# Inchworm_v0.net
KiCad netlist of a schematic drawn in Altium Designer
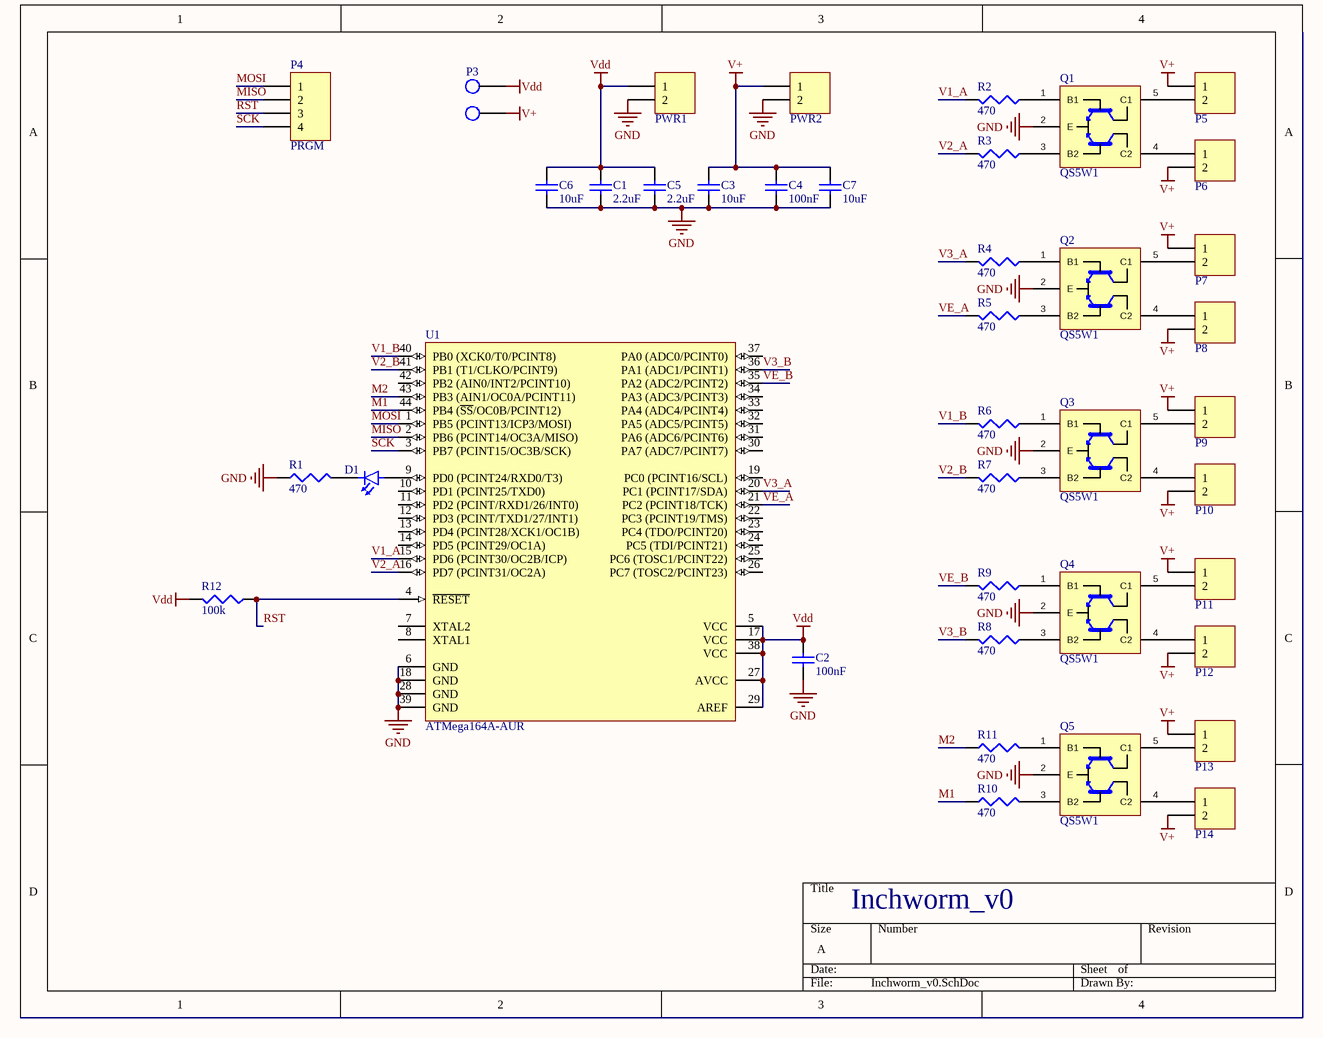
[diagram p0: Inchworm_v0.SchDoc]

(export (version "E")
  (design (tool "Eeschema 10.0.6"))
  (components
    (comp (ref "C1")
      (value "2.2uF")
      (footprint "SMD0603_cap")
      (description "Ceramic Chip Capacitor")
      (fields (field (name "Comment") "Cap"))
      (libsource (lib "Components") (part "Capacitor Ceramic"))
    )
    (comp (ref "C2")
      (value "100nF")
      (footprint "SMD0603_cap")
      (description "Ceramic Chip Capacitor")
      (fields (field (name "Comment") "Cap"))
      (libsource (lib "Components") (part "Capacitor Ceramic"))
    )
    (comp (ref "C3")
      (value "10uF")
      (footprint "SMD0603_cap")
      (description "Ceramic Chip Capacitor")
      (fields (field (name "Comment") "Cap"))
      (libsource (lib "Components") (part "Capacitor Ceramic"))
    )
    (comp (ref "C4")
      (value "100nF")
      (footprint "SMD0603_cap")
      (description "Ceramic Chip Capacitor")
      (fields (field (name "Comment") "Cap"))
      (libsource (lib "Components") (part "Capacitor Ceramic"))
    )
    (comp (ref "C5")
      (value "2.2uF")
      (footprint "SMD0603_cap")
      (description "Ceramic Chip Capacitor")
      (fields (field (name "Comment") "Cap"))
      (libsource (lib "Components") (part "Capacitor Ceramic"))
    )
    (comp (ref "C6")
      (value "10uF")
      (footprint "SMD0603_cap")
      (description "Ceramic Chip Capacitor")
      (fields (field (name "Comment") "Cap"))
      (libsource (lib "Components") (part "Capacitor Ceramic"))
    )
    (comp (ref "C7")
      (value "10uF")
      (footprint "SMD0603_cap")
      (description "Ceramic Chip Capacitor")
      (fields (field (name "Comment") "Cap"))
      (libsource (lib "Components") (part "Capacitor Ceramic"))
    )
    (comp (ref "D1")
      (value "LED")
      (footprint "SMD0603 POLARIZED")
      (libsource (lib "Components") (part "LED"))
    )
    (comp (ref "P1")
      (value "PWR1")
      (footprint "Header 2x1")
      (description "Header, 2-Pin")
      (libsource (lib "Components") (part "Header 2x1"))
    )
    (comp (ref "P2")
      (value "PWR2")
      (footprint "Header 2x1")
      (description "Header, 2-Pin")
      (libsource (lib "Components") (part "Header 2x1"))
    )
    (comp (ref "P3") (value "Via 2x1") (footprint "Via 2x1") (libsource (lib "Components") (part "Via 2x1")))
    (comp (ref "P4")
      (value "PRGM")
      (footprint "Header 4x1")
      (libsource (lib "Components") (part "Header 4x1"))
    )
    (comp (ref "P5")
      (value "Header")
      (footprint "Via 2x1_small")
      (description "Header, 2-Pin")
      (libsource (lib "Components") (part "Header 2x1"))
    )
    (comp (ref "P6")
      (value "Header")
      (footprint "Via 2x1_small")
      (description "Header, 2-Pin")
      (libsource (lib "Components") (part "Header 2x1"))
    )
    (comp (ref "P7")
      (value "Header")
      (footprint "Via 2x1_small")
      (description "Header, 2-Pin")
      (libsource (lib "Components") (part "Header 2x1"))
    )
    (comp (ref "P8")
      (value "Header")
      (footprint "Via 2x1_small")
      (description "Header, 2-Pin")
      (libsource (lib "Components") (part "Header 2x1"))
    )
    (comp (ref "P9")
      (value "Header")
      (footprint "Via 2x1_small")
      (description "Header, 2-Pin")
      (libsource (lib "Components") (part "Header 2x1"))
    )
    (comp (ref "P10")
      (value "Header")
      (footprint "Via 2x1_small")
      (description "Header, 2-Pin")
      (libsource (lib "Components") (part "Header 2x1"))
    )
    (comp (ref "P11")
      (value "Header")
      (footprint "Via 2x1_small")
      (description "Header, 2-Pin")
      (libsource (lib "Components") (part "Header 2x1"))
    )
    (comp (ref "P12")
      (value "Header")
      (footprint "Via 2x1_small")
      (description "Header, 2-Pin")
      (libsource (lib "Components") (part "Header 2x1"))
    )
    (comp (ref "P13")
      (value "Header")
      (footprint "Via 2x1_small")
      (description "Header, 2-Pin")
      (libsource (lib "Components") (part "Header 2x1"))
    )
    (comp (ref "P14")
      (value "Header")
      (footprint "Via 2x1_small")
      (description "Header, 2-Pin")
      (libsource (lib "Components") (part "Header 2x1"))
    )
    (comp (ref "Q1")
      (value "QS5W1")
      (footprint "TSMT5")
      (description "Two Medium-Power NPN BJTs with Common Emitter.  Rohm Semi.")
      (libsource (lib "Components") (part "QS5W1"))
    )
    (comp (ref "Q2")
      (value "QS5W1")
      (footprint "TSMT5")
      (description "Two Medium-Power NPN BJTs with Common Emitter.  Rohm Semi.")
      (libsource (lib "Components") (part "QS5W1"))
    )
    (comp (ref "Q3")
      (value "QS5W1")
      (footprint "TSMT5")
      (description "Two Medium-Power NPN BJTs with Common Emitter.  Rohm Semi.")
      (libsource (lib "Components") (part "QS5W1"))
    )
    (comp (ref "Q4")
      (value "QS5W1")
      (footprint "TSMT5")
      (description "Two Medium-Power NPN BJTs with Common Emitter.  Rohm Semi.")
      (libsource (lib "Components") (part "QS5W1"))
    )
    (comp (ref "Q5")
      (value "QS5W1")
      (footprint "TSMT5")
      (description "Two Medium-Power NPN BJTs with Common Emitter.  Rohm Semi.")
      (libsource (lib "Components") (part "QS5W1"))
    )
    (comp (ref "R1")
      (value "470")
      (footprint "SMD0603_res")
      (description "Resistor")
      (fields (field (name "Comment") "Res"))
      (libsource (lib "Components") (part "Resistor"))
    )
    (comp (ref "R2")
      (value "470")
      (footprint "SMD0603_res")
      (description "Resistor")
      (fields (field (name "Comment") "Res"))
      (libsource (lib "Components") (part "Resistor"))
    )
    (comp (ref "R3")
      (value "470")
      (footprint "SMD0603_res")
      (description "Resistor")
      (fields (field (name "Comment") "Res"))
      (libsource (lib "Components") (part "Resistor"))
    )
    (comp (ref "R4")
      (value "470")
      (footprint "SMD0603_res")
      (description "Resistor")
      (fields (field (name "Comment") "Res"))
      (libsource (lib "Components") (part "Resistor"))
    )
    (comp (ref "R5")
      (value "470")
      (footprint "SMD0603_res")
      (description "Resistor")
      (fields (field (name "Comment") "Res"))
      (libsource (lib "Components") (part "Resistor"))
    )
    (comp (ref "R6")
      (value "470")
      (footprint "SMD0603_res")
      (description "Resistor")
      (fields (field (name "Comment") "Res"))
      (libsource (lib "Components") (part "Resistor"))
    )
    (comp (ref "R7")
      (value "470")
      (footprint "SMD0603_res")
      (description "Resistor")
      (fields (field (name "Comment") "Res"))
      (libsource (lib "Components") (part "Resistor"))
    )
    (comp (ref "R8")
      (value "470")
      (footprint "SMD0603_res")
      (description "Resistor")
      (fields (field (name "Comment") "Res"))
      (libsource (lib "Components") (part "Resistor"))
    )
    (comp (ref "R9")
      (value "470")
      (footprint "SMD0603_res")
      (description "Resistor")
      (fields (field (name "Comment") "Res"))
      (libsource (lib "Components") (part "Resistor"))
    )
    (comp (ref "R10")
      (value "470")
      (footprint "SMD0603_res")
      (description "Resistor")
      (fields (field (name "Comment") "Res"))
      (libsource (lib "Components") (part "Resistor"))
    )
    (comp (ref "R11")
      (value "470")
      (footprint "SMD0603_res")
      (description "Resistor")
      (fields (field (name "Comment") "Res"))
      (libsource (lib "Components") (part "Resistor"))
    )
    (comp (ref "R12")
      (value "100k")
      (footprint "SMD0603_res")
      (description "Resistor")
      (fields (field (name "Comment") "Res"))
      (libsource (lib "Components") (part "Resistor"))
    )
    (comp (ref "U1")
      (value "ATMega164A-AUR")
      (footprint "TQFP44")
      (libsource (lib "Components") (part "ATMega164A-AUR"))
    )
  )
  (nets
    (net (code "1") (name "/M1") (class "Default")
      (node (ref "R10") (pin "1") (pinfunction "1_1") (pintype "passive"))
      (node (ref "U1") (pin "44") (pinfunction "PB4_(~{SS}/OC0B/PCINT12)_44") (pintype "bidirectional"))
    )
    (net (code "2") (name "/M2") (class "Default")
      (node (ref "R11") (pin "1") (pinfunction "1_1") (pintype "passive"))
      (node (ref "U1") (pin "43") (pinfunction "PB3_(AIN1/OC0A/PCINT11)_43") (pintype "bidirectional"))
    )
    (net (code "3") (name "/MISO") (class "Default")
      (node (ref "P4") (pin "2") (pinfunction "2_2") (pintype "passive"))
      (node (ref "U1") (pin "2") (pinfunction "PB6_(PCINT14/OC3A/MISO)_2") (pintype "bidirectional"))
    )
    (net (code "4") (name "/MOSI") (class "Default")
      (node (ref "P4") (pin "1") (pinfunction "1_1") (pintype "passive"))
      (node (ref "U1") (pin "1") (pinfunction "PB5_(PCINT13/ICP3/MOSI)_1") (pintype "bidirectional"))
    )
    (net (code "5") (name "/RST") (class "Default")
      (node (ref "P4") (pin "3") (pinfunction "3_3") (pintype "passive"))
      (node (ref "R12") (pin "1") (pinfunction "1_1") (pintype "passive"))
      (node (ref "U1") (pin "4") (pinfunction "~{RESET}_4") (pintype "input"))
    )
    (net (code "6") (name "/SCK") (class "Default")
      (node (ref "P4") (pin "4") (pinfunction "4_4") (pintype "passive"))
      (node (ref "U1") (pin "3") (pinfunction "PB7_(PCINT15/OC3B/SCK)_3") (pintype "bidirectional"))
    )
    (net (code "7") (name "/V1_A") (class "Default")
      (node (ref "R2") (pin "2") (pinfunction "2_2") (pintype "passive"))
      (node (ref "U1") (pin "15") (pinfunction "PD6_(PCINT30/OC2B/ICP)_15") (pintype "bidirectional"))
    )
    (net (code "8") (name "/V1_B") (class "Default")
      (node (ref "R6") (pin "2") (pinfunction "2_2") (pintype "passive"))
      (node (ref "U1") (pin "40") (pinfunction "PB0_(XCK0/T0/PCINT8)_40") (pintype "bidirectional"))
    )
    (net (code "9") (name "/V2_A") (class "Default")
      (node (ref "R3") (pin "2") (pinfunction "2_2") (pintype "passive"))
      (node (ref "U1") (pin "16") (pinfunction "PD7_(PCINT31/OC2A)_16") (pintype "bidirectional"))
    )
    (net (code "10") (name "/V2_B") (class "Default")
      (node (ref "R7") (pin "2") (pinfunction "2_2") (pintype "passive"))
      (node (ref "U1") (pin "41") (pinfunction "PB1_(T1/CLKO/PCINT9)_41") (pintype "bidirectional"))
    )
    (net (code "11") (name "/V3_A") (class "Default")
      (node (ref "R4") (pin "2") (pinfunction "2_2") (pintype "passive"))
      (node (ref "U1") (pin "20") (pinfunction "PC1_(PCINT17/SDA)_20") (pintype "bidirectional"))
    )
    (net (code "12") (name "/V3_B") (class "Default")
      (node (ref "R8") (pin "2") (pinfunction "2_2") (pintype "passive"))
      (node (ref "U1") (pin "36") (pinfunction "PA1_(ADC1/PCINT1)_36") (pintype "bidirectional"))
    )
    (net (code "13") (name "/VE_A") (class "Default")
      (node (ref "R5") (pin "2") (pinfunction "2_2") (pintype "passive"))
      (node (ref "U1") (pin "21") (pinfunction "PC2_(PCINT18/TCK)_21") (pintype "bidirectional"))
    )
    (net (code "14") (name "/VE_B") (class "Default")
      (node (ref "R9") (pin "2") (pinfunction "2_2") (pintype "passive"))
      (node (ref "U1") (pin "35") (pinfunction "PA2_(ADC2/PCINT2)_35") (pintype "bidirectional"))
    )
    (net (code "15") (name "GND") (class "Default")
      (node (ref "C1") (pin "1") (pinfunction "1_1") (pintype "passive"))
      (node (ref "C2") (pin "1") (pinfunction "1_1") (pintype "passive"))
      (node (ref "C3") (pin "1") (pinfunction "1_1") (pintype "passive"))
      (node (ref "C4") (pin "1") (pinfunction "1_1") (pintype "passive"))
      (node (ref "C5") (pin "1") (pinfunction "1_1") (pintype "passive"))
      (node (ref "C6") (pin "1") (pinfunction "1_1") (pintype "passive"))
      (node (ref "C7") (pin "1") (pinfunction "1_1") (pintype "passive"))
      (node (ref "P1") (pin "2") (pinfunction "2_2") (pintype "passive"))
      (node (ref "P2") (pin "2") (pinfunction "2_2") (pintype "passive"))
      (node (ref "Q1") (pin "2") (pinfunction "E_2") (pintype "passive"))
      (node (ref "Q2") (pin "2") (pinfunction "E_2") (pintype "passive"))
      (node (ref "Q3") (pin "2") (pinfunction "E_2") (pintype "passive"))
      (node (ref "Q4") (pin "2") (pinfunction "E_2") (pintype "passive"))
      (node (ref "Q5") (pin "2") (pinfunction "E_2") (pintype "passive"))
      (node (ref "R1") (pin "1") (pinfunction "1_1") (pintype "passive"))
      (node (ref "U1") (pin "18") (pinfunction "GND_18") (pintype "power_in"))
      (node (ref "U1") (pin "28") (pinfunction "GND_28") (pintype "power_in"))
      (node (ref "U1") (pin "39") (pinfunction "GND_39") (pintype "power_in"))
      (node (ref "U1") (pin "6") (pinfunction "GND_6") (pintype "power_in"))
    )
    (net (code "16") (name "Net-(D1-Anode_(+))") (class "Default")
      (node (ref "D1") (pin "1") (pinfunction "Anode_(+)_1") (pintype "passive"))
      (node (ref "U1") (pin "9") (pinfunction "PD0_(PCINT24/RXD0/T3)_9") (pintype "bidirectional"))
    )
    (net (code "17") (name "Net-(D1-Cathode_(-))") (class "Default")
      (node (ref "D1") (pin "2") (pinfunction "Cathode_(-)_2") (pintype "passive"))
      (node (ref "R1") (pin "2") (pinfunction "2_2") (pintype "passive"))
    )
    (net (code "18") (name "Net-(Q1-B1)") (class "Default")
      (node (ref "Q1") (pin "1") (pinfunction "B1_1") (pintype "passive"))
      (node (ref "R2") (pin "1") (pinfunction "1_1") (pintype "passive"))
    )
    (net (code "19") (name "Net-(Q1-B2)") (class "Default")
      (node (ref "Q1") (pin "3") (pinfunction "B2_3") (pintype "passive"))
      (node (ref "R3") (pin "1") (pinfunction "1_1") (pintype "passive"))
    )
    (net (code "20") (name "Net-(Q1-C1)") (class "Default")
      (node (ref "P5") (pin "2") (pinfunction "2_2") (pintype "passive"))
      (node (ref "Q1") (pin "5") (pinfunction "C1_5") (pintype "passive"))
    )
    (net (code "21") (name "Net-(Q1-C2)") (class "Default")
      (node (ref "P6") (pin "1") (pinfunction "1_1") (pintype "passive"))
      (node (ref "Q1") (pin "4") (pinfunction "C2_4") (pintype "passive"))
    )
    (net (code "22") (name "Net-(Q2-B1)") (class "Default")
      (node (ref "Q2") (pin "1") (pinfunction "B1_1") (pintype "passive"))
      (node (ref "R4") (pin "1") (pinfunction "1_1") (pintype "passive"))
    )
    (net (code "23") (name "Net-(Q2-B2)") (class "Default")
      (node (ref "Q2") (pin "3") (pinfunction "B2_3") (pintype "passive"))
      (node (ref "R5") (pin "1") (pinfunction "1_1") (pintype "passive"))
    )
    (net (code "24") (name "Net-(Q2-C1)") (class "Default")
      (node (ref "P7") (pin "2") (pinfunction "2_2") (pintype "passive"))
      (node (ref "Q2") (pin "5") (pinfunction "C1_5") (pintype "passive"))
    )
    (net (code "25") (name "Net-(Q2-C2)") (class "Default")
      (node (ref "P8") (pin "1") (pinfunction "1_1") (pintype "passive"))
      (node (ref "Q2") (pin "4") (pinfunction "C2_4") (pintype "passive"))
    )
    (net (code "26") (name "Net-(Q3-B1)") (class "Default")
      (node (ref "Q3") (pin "1") (pinfunction "B1_1") (pintype "passive"))
      (node (ref "R6") (pin "1") (pinfunction "1_1") (pintype "passive"))
    )
    (net (code "27") (name "Net-(Q3-B2)") (class "Default")
      (node (ref "Q3") (pin "3") (pinfunction "B2_3") (pintype "passive"))
      (node (ref "R7") (pin "1") (pinfunction "1_1") (pintype "passive"))
    )
    (net (code "28") (name "Net-(Q3-C1)") (class "Default")
      (node (ref "P9") (pin "2") (pinfunction "2_2") (pintype "passive"))
      (node (ref "Q3") (pin "5") (pinfunction "C1_5") (pintype "passive"))
    )
    (net (code "29") (name "Net-(Q3-C2)") (class "Default")
      (node (ref "P10") (pin "1") (pinfunction "1_1") (pintype "passive"))
      (node (ref "Q3") (pin "4") (pinfunction "C2_4") (pintype "passive"))
    )
    (net (code "30") (name "Net-(Q4-B1)") (class "Default")
      (node (ref "Q4") (pin "1") (pinfunction "B1_1") (pintype "passive"))
      (node (ref "R9") (pin "1") (pinfunction "1_1") (pintype "passive"))
    )
    (net (code "31") (name "Net-(Q4-B2)") (class "Default")
      (node (ref "Q4") (pin "3") (pinfunction "B2_3") (pintype "passive"))
      (node (ref "R8") (pin "1") (pinfunction "1_1") (pintype "passive"))
    )
    (net (code "32") (name "Net-(Q4-C1)") (class "Default")
      (node (ref "P11") (pin "2") (pinfunction "2_2") (pintype "passive"))
      (node (ref "Q4") (pin "5") (pinfunction "C1_5") (pintype "passive"))
    )
    (net (code "33") (name "Net-(Q4-C2)") (class "Default")
      (node (ref "P12") (pin "1") (pinfunction "1_1") (pintype "passive"))
      (node (ref "Q4") (pin "4") (pinfunction "C2_4") (pintype "passive"))
    )
    (net (code "34") (name "Net-(Q5-B1)") (class "Default")
      (node (ref "Q5") (pin "1") (pinfunction "B1_1") (pintype "passive"))
      (node (ref "R11") (pin "2") (pinfunction "2_2") (pintype "passive"))
    )
    (net (code "35") (name "Net-(Q5-B2)") (class "Default")
      (node (ref "Q5") (pin "3") (pinfunction "B2_3") (pintype "passive"))
      (node (ref "R10") (pin "2") (pinfunction "2_2") (pintype "passive"))
    )
    (net (code "36") (name "Net-(Q5-C1)") (class "Default")
      (node (ref "P13") (pin "2") (pinfunction "2_2") (pintype "passive"))
      (node (ref "Q5") (pin "5") (pinfunction "C1_5") (pintype "passive"))
    )
    (net (code "37") (name "Net-(Q5-C2)") (class "Default")
      (node (ref "P14") (pin "1") (pinfunction "1_1") (pintype "passive"))
      (node (ref "Q5") (pin "4") (pinfunction "C2_4") (pintype "passive"))
    )
    (net (code "38") (name "V+") (class "Default")
      (node (ref "C3") (pin "2") (pinfunction "2_2") (pintype "passive"))
      (node (ref "C4") (pin "2") (pinfunction "2_2") (pintype "passive"))
      (node (ref "C7") (pin "2") (pinfunction "2_2") (pintype "passive"))
      (node (ref "P10") (pin "2") (pinfunction "2_2") (pintype "passive"))
      (node (ref "P11") (pin "1") (pinfunction "1_1") (pintype "passive"))
      (node (ref "P12") (pin "2") (pinfunction "2_2") (pintype "passive"))
      (node (ref "P13") (pin "1") (pinfunction "1_1") (pintype "passive"))
      (node (ref "P14") (pin "2") (pinfunction "2_2") (pintype "passive"))
      (node (ref "P2") (pin "1") (pinfunction "1_1") (pintype "passive"))
      (node (ref "P3") (pin "2") (pintype "passive"))
      (node (ref "P5") (pin "1") (pinfunction "1_1") (pintype "passive"))
      (node (ref "P6") (pin "2") (pinfunction "2_2") (pintype "passive"))
      (node (ref "P7") (pin "1") (pinfunction "1_1") (pintype "passive"))
      (node (ref "P8") (pin "2") (pinfunction "2_2") (pintype "passive"))
      (node (ref "P9") (pin "1") (pinfunction "1_1") (pintype "passive"))
    )
    (net (code "39") (name "Vdd") (class "Default")
      (node (ref "C1") (pin "2") (pinfunction "2_2") (pintype "passive"))
      (node (ref "C2") (pin "2") (pinfunction "2_2") (pintype "passive"))
      (node (ref "C5") (pin "2") (pinfunction "2_2") (pintype "passive"))
      (node (ref "C6") (pin "2") (pinfunction "2_2") (pintype "passive"))
      (node (ref "P1") (pin "1") (pinfunction "1_1") (pintype "passive"))
      (node (ref "P3") (pin "1") (pintype "passive"))
      (node (ref "R12") (pin "2") (pinfunction "2_2") (pintype "passive"))
      (node (ref "U1") (pin "17") (pinfunction "VCC_17") (pintype "power_in"))
      (node (ref "U1") (pin "27") (pinfunction "AVCC_27") (pintype "power_in"))
      (node (ref "U1") (pin "29") (pinfunction "AREF_29") (pintype "power_in"))
      (node (ref "U1") (pin "38") (pinfunction "VCC_38") (pintype "power_in"))
      (node (ref "U1") (pin "5") (pinfunction "VCC_5") (pintype "power_in"))
    )
    (net (code "40") (name "unconnected-(U1-PA0_(ADC0{slash}PCINT0)-Pad37)") (class "Default")
      (node (ref "U1") (pin "37") (pinfunction "PA0_(ADC0/PCINT0)_37") (pintype "bidirectional"))
    )
    (net (code "41") (name "unconnected-(U1-PA3_(ADC3{slash}PCINT3)-Pad34)") (class "Default")
      (node (ref "U1") (pin "34") (pinfunction "PA3_(ADC3/PCINT3)_34") (pintype "bidirectional"))
    )
    (net (code "42") (name "unconnected-(U1-PA4_(ADC4{slash}PCINT4)-Pad33)") (class "Default")
      (node (ref "U1") (pin "33") (pinfunction "PA4_(ADC4/PCINT4)_33") (pintype "bidirectional"))
    )
    (net (code "43") (name "unconnected-(U1-PA5_(ADC5{slash}PCINT5)-Pad32)") (class "Default")
      (node (ref "U1") (pin "32") (pinfunction "PA5_(ADC5/PCINT5)_32") (pintype "bidirectional"))
    )
    (net (code "44") (name "unconnected-(U1-PA6_(ADC6{slash}PCINT6)-Pad31)") (class "Default")
      (node (ref "U1") (pin "31") (pinfunction "PA6_(ADC6/PCINT6)_31") (pintype "bidirectional"))
    )
    (net (code "45") (name "unconnected-(U1-PA7_(ADC7{slash}PCINT7)-Pad30)") (class "Default")
      (node (ref "U1") (pin "30") (pinfunction "PA7_(ADC7/PCINT7)_30") (pintype "bidirectional"))
    )
    (net (code "46") (name "unconnected-(U1-PB2_(AIN0{slash}INT2{slash}PCINT10)-Pad42)") (class "Default")
      (node (ref "U1") (pin "42") (pinfunction "PB2_(AIN0/INT2/PCINT10)_42") (pintype "bidirectional"))
    )
    (net (code "47") (name "unconnected-(U1-PC0_(PCINT16{slash}SCL)-Pad19)") (class "Default")
      (node (ref "U1") (pin "19") (pinfunction "PC0_(PCINT16/SCL)_19") (pintype "bidirectional"))
    )
    (net (code "48") (name "unconnected-(U1-PC3_(PCINT19{slash}TMS)-Pad22)") (class "Default")
      (node (ref "U1") (pin "22") (pinfunction "PC3_(PCINT19/TMS)_22") (pintype "bidirectional"))
    )
    (net (code "49") (name "unconnected-(U1-PC4_(TDO{slash}PCINT20)-Pad23)") (class "Default")
      (node (ref "U1") (pin "23") (pinfunction "PC4_(TDO/PCINT20)_23") (pintype "bidirectional"))
    )
    (net (code "50") (name "unconnected-(U1-PC5_(TDI{slash}PCINT21)-Pad24)") (class "Default")
      (node (ref "U1") (pin "24") (pinfunction "PC5_(TDI/PCINT21)_24") (pintype "bidirectional"))
    )
    (net (code "51") (name "unconnected-(U1-PC6_(TOSC1{slash}PCINT22)-Pad25)") (class "Default")
      (node (ref "U1") (pin "25") (pinfunction "PC6_(TOSC1/PCINT22)_25") (pintype "bidirectional"))
    )
    (net (code "52") (name "unconnected-(U1-PC7_(TOSC2{slash}PCINT23)-Pad26)") (class "Default")
      (node (ref "U1") (pin "26") (pinfunction "PC7_(TOSC2/PCINT23)_26") (pintype "bidirectional"))
    )
    (net (code "53") (name "unconnected-(U1-PD1_(PCINT25{slash}TXD0)-Pad10)") (class "Default")
      (node (ref "U1") (pin "10") (pinfunction "PD1_(PCINT25/TXD0)_10") (pintype "bidirectional"))
    )
    (net (code "54") (name "unconnected-(U1-PD2_(PCINT{slash}RXD1{slash}26{slash}INT0)-Pad11)") (class "Default")
      (node (ref "U1") (pin "11") (pinfunction "PD2_(PCINT/RXD1/26/INT0)_11") (pintype "bidirectional"))
    )
    (net (code "55") (name "unconnected-(U1-PD3_(PCINT{slash}TXD1{slash}27{slash}INT1)-Pad12)") (class "Default")
      (node (ref "U1") (pin "12") (pinfunction "PD3_(PCINT/TXD1/27/INT1)_12") (pintype "bidirectional"))
    )
    (net (code "56") (name "unconnected-(U1-PD4_(PCINT28{slash}XCK1{slash}OC1B)-Pad13)") (class "Default")
      (node (ref "U1") (pin "13") (pinfunction "PD4_(PCINT28/XCK1/OC1B)_13") (pintype "bidirectional"))
    )
    (net (code "57") (name "unconnected-(U1-PD5_(PCINT29{slash}OC1A)-Pad14)") (class "Default")
      (node (ref "U1") (pin "14") (pinfunction "PD5_(PCINT29/OC1A)_14") (pintype "bidirectional"))
    )
    (net (code "58") (name "unconnected-(U1-XTAL1-Pad8)") (class "Default")
      (node (ref "U1") (pin "8") (pinfunction "XTAL1_8") (pintype "passive"))
    )
    (net (code "59") (name "unconnected-(U1-XTAL2-Pad7)") (class "Default")
      (node (ref "U1") (pin "7") (pinfunction "XTAL2_7") (pintype "passive"))
    )
  )
)
